# POWER_SUPPLY_20V_4A.net
KiCad netlist of a schematic drawn in Altium Designer
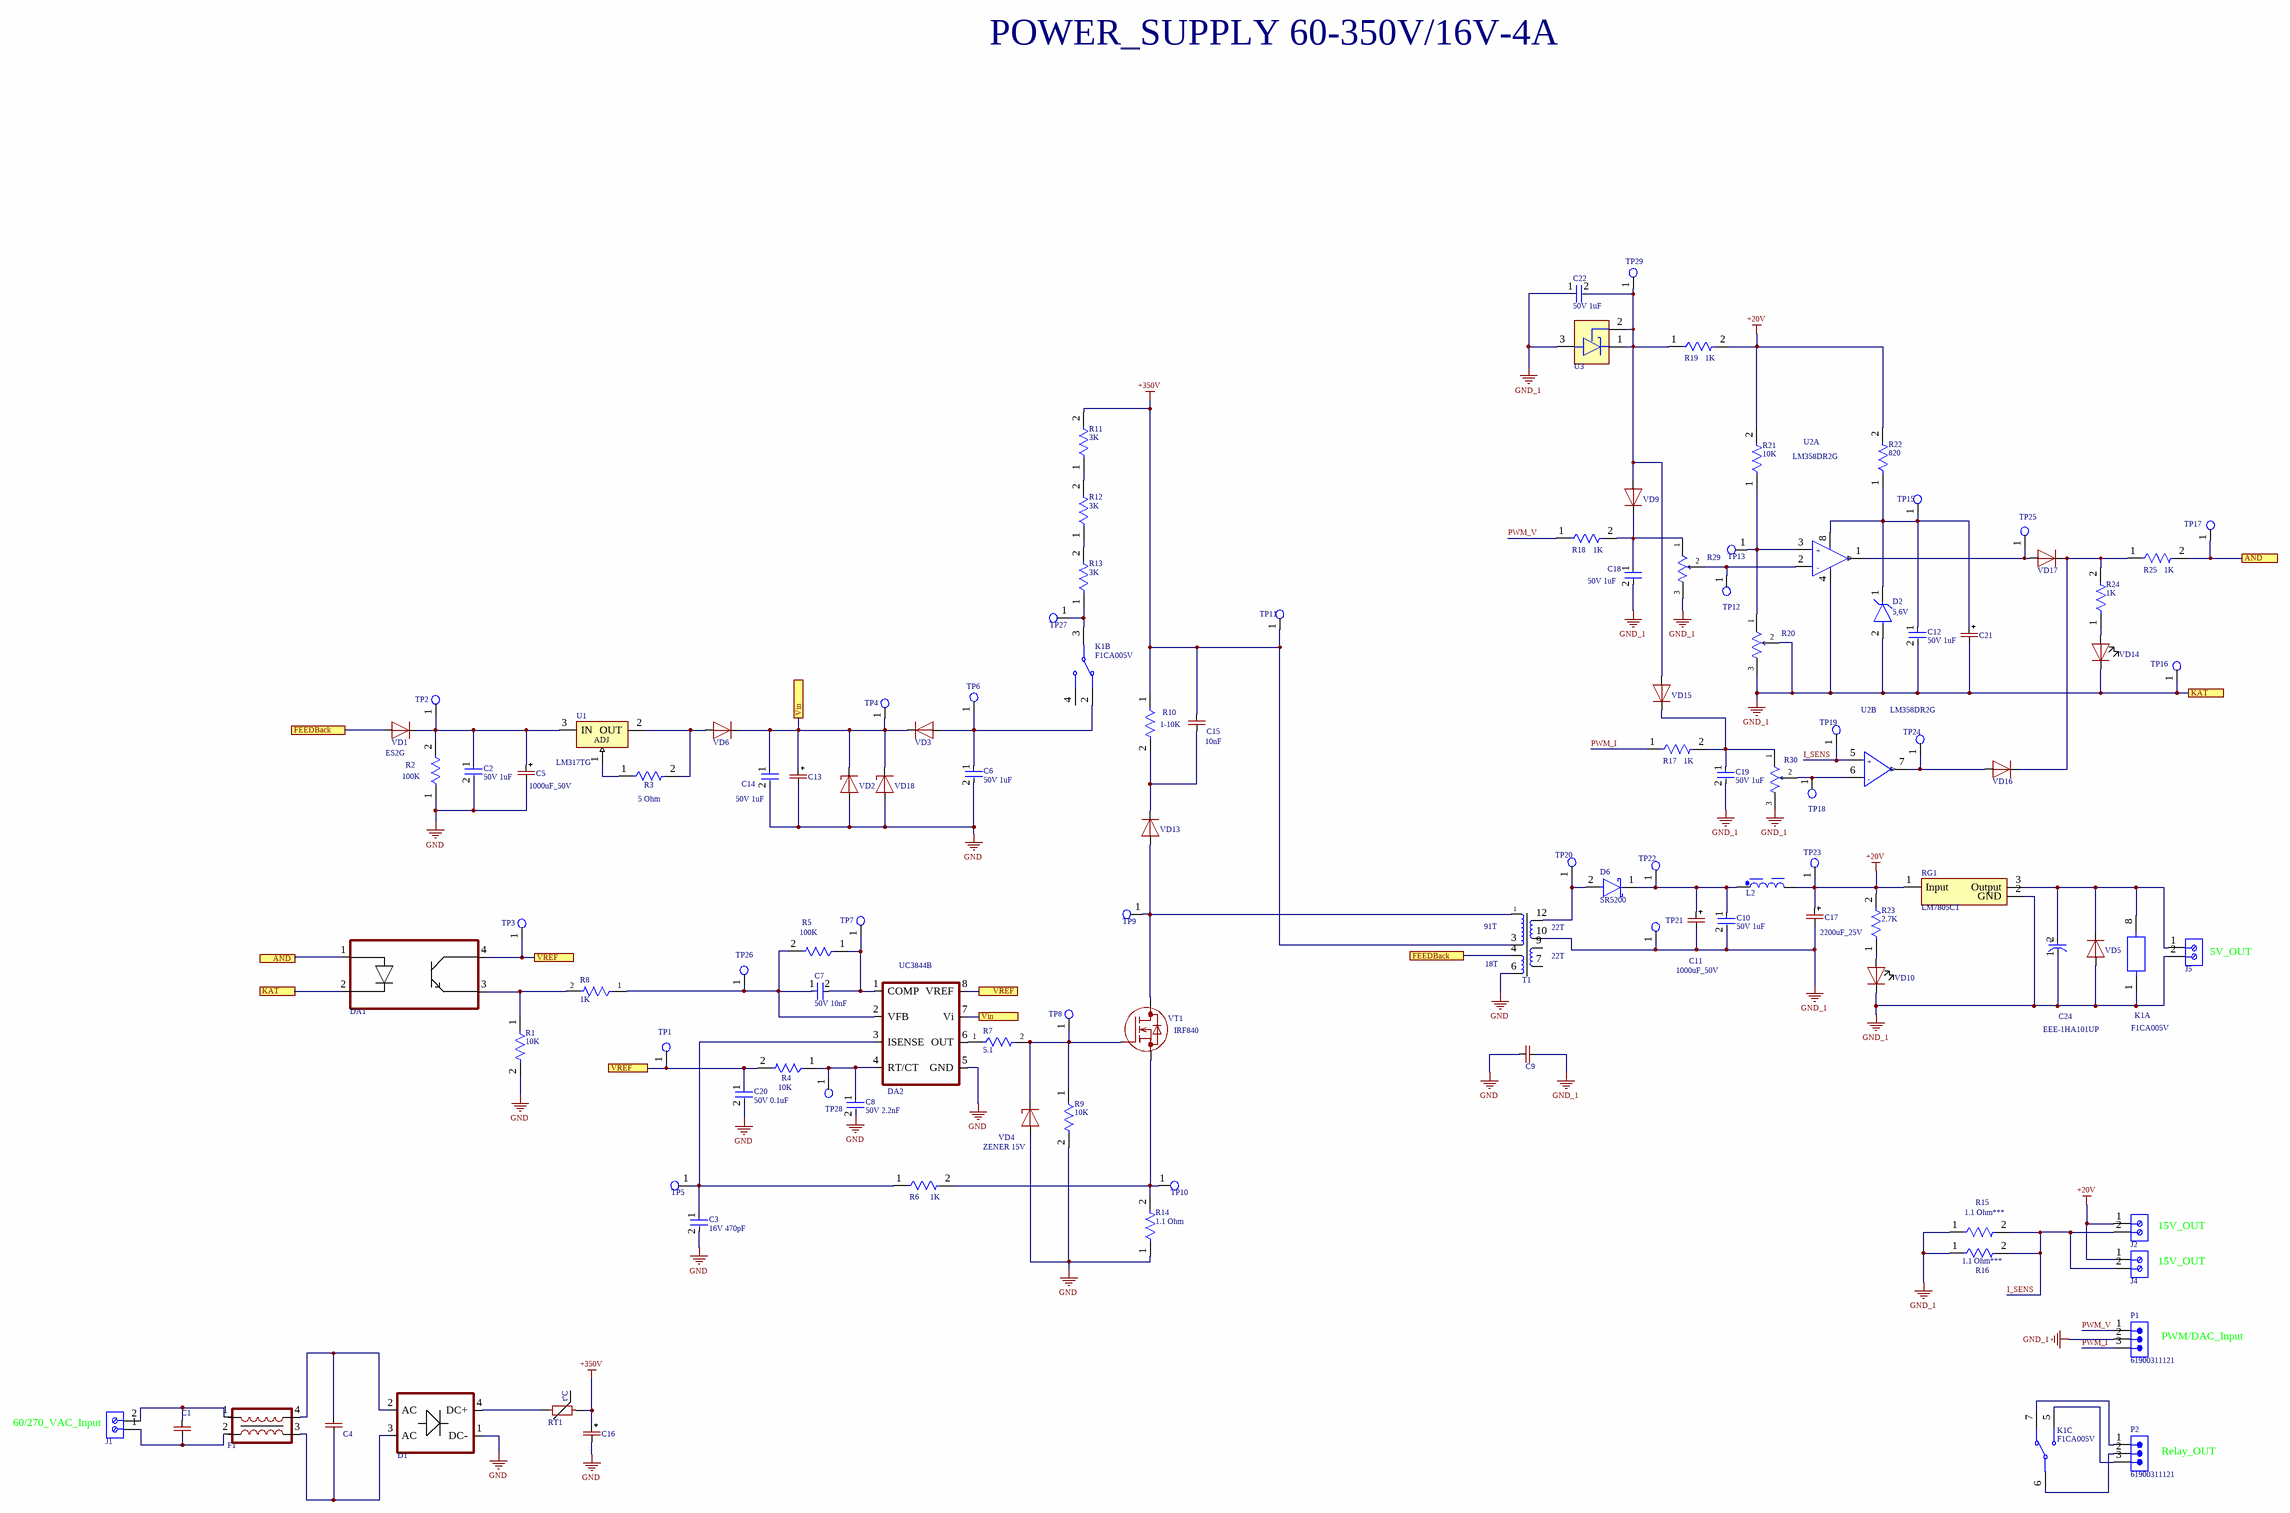
[diagram p0: POWER_SUPPLY_20V_4A.SchDoc]

(export (version "E")
  (design (tool "Eeschema 10.0.6"))
  (components
    (comp (ref "C1")
      (value "CAP-NON-POLAR")
      (footprint "CAP-V15")
      (libsource (lib "0.47uF 310V") (part "CAP-NON-POLAR"))
    )
    (comp (ref "C2")
      (value "50V 1uF")
      (footprint "FP-C0805C-DN-IPC_A")
      (description "CAP CER 0.22UF 50V X7R 0805")
      (fields
        (field (name "MANUFACTURER") "KEMET")
        (field (name "OCTOPART") "https://octopart.com/c0805c224k5ractu-kemet-144670")
      )
      (libsource (lib "Pasive_components") (part "CMP-1036-04552-2"))
    )
    (comp (ref "C3")
      (value "16V 470pF")
      (footprint "FP-C0805C-DN-IPC_A")
      (description "CAP CER 0.22UF 50V X7R 0805")
      (fields
        (field (name "MANUFACTURER") "KEMET")
        (field (name "OCTOPART") "https://octopart.com/c0805c224k5ractu-kemet-144670")
      )
      (libsource (lib "Pasive_components") (part "CMP-1036-04552-2"))
    )
    (comp (ref "C4")
      (value "CAP-NON-POLAR")
      (footprint "CAP-V15")
      (libsource (lib "0.47uF 310V") (part "CAP-NON-POLAR"))
    )
    (comp (ref "C5")
      (value "1000uF_50V")
      (footprint "CAPPOL-12x25")
      (description "1000uF_50V  12x25(13x26mm)")
      (libsource (lib "PASSIVE_COMPONENTS") (part "CAP-POLAR"))
    )
    (comp (ref "C6")
      (value "50V 1uF")
      (footprint "FP-C0805C-DN-IPC_A")
      (description "CAP CER 0.22UF 50V X7R 0805")
      (fields
        (field (name "MANUFACTURER") "KEMET")
        (field (name "OCTOPART") "https://octopart.com/c0805c224k5ractu-kemet-144670")
      )
      (libsource (lib "Pasive_components") (part "CMP-1036-04552-2"))
    )
    (comp (ref "C7")
      (value "50V 10nF")
      (footprint "FP-C0805C-DN-IPC_A")
      (description "CAP CER 0.22UF 50V X7R 0805")
      (fields
        (field (name "MANUFACTURER") "KEMET")
        (field (name "OCTOPART") "https://octopart.com/c0805c224k5ractu-kemet-144670")
      )
      (libsource (lib "Pasive_components") (part "CMP-1036-04552-2"))
    )
    (comp (ref "C8")
      (value "50V 2.2nF")
      (footprint "FP-C0805C-DN-IPC_A")
      (description "CAP CER 2.2nF 50V X7R 0805")
      (fields
        (field (name "MANUFACTURER") "KEMET")
        (field (name "OCTOPART") "https://octopart.com/c0805c224k5ractu-kemet-144670")
      )
      (libsource (lib "Pasive_components") (part "CMP-1036-04552-2"))
    )
    (comp (ref "C9") (value "CAP-V") (footprint "CAP-V") (libsource (lib "2200") (part "CAP-V")))
    (comp (ref "C10")
      (value "50V 1uF")
      (footprint "FP-C0805C-DN-IPC_A")
      (description "CAP CER 0.22UF 50V X7R 0805")
      (fields
        (field (name "MANUFACTURER") "KEMET")
        (field (name "OCTOPART") "https://octopart.com/c0805c224k5ractu-kemet-144670")
      )
      (libsource (lib "Pasive_components") (part "CMP-1036-04552-2"))
    )
    (comp (ref "C11")
      (value "1000uF_50V")
      (footprint "CAPPOL-12x25")
      (libsource (lib "PASSIVE_COMPONENTS") (part "CAP-POLAR"))
    )
    (comp (ref "C12")
      (value "50V 1uF")
      (footprint "FP-C0805C-DN-IPC_A")
      (description "CAP CER 0.22UF 50V X7R 0805")
      (fields
        (field (name "MANUFACTURER") "KEMET")
        (field (name "OCTOPART") "https://octopart.com/c0805c224k5ractu-kemet-144670")
      )
      (libsource (lib "Pasive_components") (part "CMP-1036-04552-2"))
    )
    (comp (ref "C13")
      (value "CAP-POLAR")
      (footprint "CAPPOL-12x25")
      (libsource (lib "PASSIVE_COMPONENTS") (part "CAP-POLAR"))
    )
    (comp (ref "C14")
      (value "50V 1uF")
      (footprint "FP-C0805C-DN-IPC_A")
      (description "CAP CER 0.22UF 50V X7R 0805")
      (fields
        (field (name "MANUFACTURER") "KEMET")
        (field (name "OCTOPART") "https://octopart.com/c0805c224k5ractu-kemet-144670")
      )
      (libsource (lib "Pasive_components") (part "CMP-1036-04552-2"))
    )
    (comp (ref "C15") (value "10nF") (footprint "CAP-V") (libsource (lib "2200") (part "CAP-V")))
    (comp (ref "C16")
      (value "CAP-POLAR")
      (footprint "CAP 100uF_500V 22x40mm")
      (libsource (lib "PASSIVE_COMPONENTS") (part "CAP-POLAR"))
    )
    (comp (ref "C17")
      (value "2200uF_25V")
      (footprint "CAPPOL-12x25")
      (libsource (lib "PASSIVE_COMPONENTS") (part "CAP-POLAR"))
    )
    (comp (ref "C18")
      (value "50V 1uF")
      (footprint "FP-C0805C-DN-IPC_A")
      (description "CAP CER 0.22UF 50V X7R 0805")
      (fields
        (field (name "MANUFACTURER") "KEMET")
        (field (name "OCTOPART") "https://octopart.com/c0805c224k5ractu-kemet-144670")
      )
      (libsource (lib "Pasive_components") (part "CMP-1036-04552-2"))
    )
    (comp (ref "C19")
      (value "50V 1uF")
      (footprint "FP-C0805C-DN-IPC_A")
      (description "CAP CER 0.22UF 50V X7R 0805")
      (fields
        (field (name "MANUFACTURER") "KEMET")
        (field (name "OCTOPART") "https://octopart.com/c0805c224k5ractu-kemet-144670")
      )
      (libsource (lib "Pasive_components") (part "CMP-1036-04552-2"))
    )
    (comp (ref "C20")
      (value "50V 0.1uF")
      (footprint "FP-C0805C-DN-IPC_A")
      (description "CAP CER 0.1UF 50V X7R 0805")
      (fields
        (field (name "MANUFACTURER") "KEMET")
        (field (name "OCTOPART") "https://octopart.com/c0805c224k5ractu-kemet-144670")
      )
      (libsource (lib "Pasive_components") (part "CMP-1036-04552-2"))
    )
    (comp (ref "C21")
      (value "CAP-POLAR")
      (footprint "CAP-TAN-C")
      (libsource (lib "PASSIVE_COMPONENTS") (part "CAP-POLAR"))
    )
    (comp (ref "C22")
      (value "50V 1uF")
      (footprint "FP-C0805C-DN-IPC_A")
      (description "CAP CER 0.22UF 50V X7R 0805")
      (fields
        (field (name "MANUFACTURER") "KEMET")
        (field (name "OCTOPART") "https://octopart.com/c0805c224k5ractu-kemet-144670")
      )
      (libsource (lib "Pasive_components") (part "CMP-1036-04552-2"))
    )
    (comp (ref "C24")
      (value "EEE-1HA101UP")
      (footprint "FP-SF-MFG")
      (description "CAP ALUM 100UF 20% 50V SMD")
      (fields
        (field (name "MANUFACTURER") "Panasonic")
        (field (name "OCTOPART") "https://octopart.com/eee-1ha101up-panasonic-55396734")
      )
      (libsource (lib "Pasive_components") (part "CMP-05427-000015-1"))
    )
    (comp (ref "D1") (value "RS40X") (footprint "RS40X") (libsource (lib "RS40X") (part "RS40X")))
    (comp (ref "D2")
      (value "5,6V")
      (footprint "FP-SB-V-3906_04-031_4-MFG")
      (description "DIODE ZENER 8.2V 500MW DO35")
      (fields (field (name "TOLERANCE") "2%"))
      (libsource (lib "Altium Content Vault") (part "f813f71cba58e380607f5dd3caf9714"))
    )
    (comp (ref "D6")
      (value "SR5200")
      (footprint "SR5100(DO-201AD")
      (libsource (lib "SR5100") (part "SR5100"))
    )
    (comp (ref "DA1") (value "PC817") (footprint "4-SMD") (libsource (lib "PC817") (part "PC817")))
    (comp (ref "DA2") (value "UC3844B") (footprint "SOIC8-150") (libsource (lib "UC3842B") (part "UC3842B")))
    (comp (ref "F1") (value "FILTER") (footprint "FILTER_1") (libsource (lib "FILTER") (part "FILTER")))
    (comp (ref "J1")
      (value "691101710002")
      (footprint "691101710002")
      (description "WR-TBL Series 101 Horizontal Entry Modular, THT, pitch 5mm, 2p")
      (fields (field (name "MANUFACTURER") "Wurth Elektronik"))
      (libsource (lib "Altium_WR-TBL (rev22b)") (part "691101710002"))
    )
    (comp (ref "J2")
      (value "~")
      (footprint "691101710002")
      (description "WR-TBL Series 101 Horizontal Entry Modular, THT, pitch 5mm, 2p")
      (fields
        (field (name "MANUFACTURER PART NUMBER") "691101710002")
        (field (name "MANUFACTURER") "Wurth Elektronik")
      )
      (libsource (lib "Altium_WR-TBL (rev23d)") (part "691101710002"))
    )
    (comp (ref "J4")
      (value "691101710002")
      (footprint "691101710002")
      (description "WR-TBL Series 101 Horizontal Entry Modular, THT, pitch 5mm, 2p")
      (fields (field (name "MANUFACTURER") "Wurth Elektronik"))
      (libsource (lib "Altium_WR-TBL (rev23d)") (part "691101710002"))
    )
    (comp (ref "J5")
      (value "691101710002")
      (footprint "691101710002")
      (description "WR-TBL Series 101 Horizontal Entry Modular, THT, pitch 5mm, 2p")
      (fields (field (name "MANUFACTURER") "Wurth Elektronik"))
      (libsource (lib "Altium_WR-TBL (rev23f)") (part "691101710002"))
    )
    (comp (ref "K1")
      (value "F1CA005V")
      (footprint "Relay_F1CA005V_Omron")
      (libsource (lib "Relay_F1CA005V") (part "F1CA005V"))
    )
    (comp (ref "L2")
      (value "1.2µH, 7.4A")
      (footprint "WE-PD2_1054")
      (description "WE-PD2 SMT Power Inductor, size 1054, 1.2µH, 7.4A, 0.006Ω")
      (fields
        (field (name "MANUFACTURER PART NUMBER") "744776012")
        (field (name "MANUFACTURER") "Wurth Elektronik")
      )
      (libsource (lib "WE-PD2 (rev22d)") (part "744776012"))
    )
    (comp (ref "P1")
      (value "61900311121")
      (footprint "61900311121")
      (description "WR-WTB THT Male Vertical Locking Header, pitch 2.54mm, 3pins")
      (fields (field (name "MANUFACTURER") "Wurth Elektronik"))
      (libsource (lib "Altium_WR-WTB (rev22b)") (part "61900311121"))
    )
    (comp (ref "P2")
      (value "61900311121")
      (footprint "61900311121")
      (description "WR-WTB THT Male Vertical Locking Header, pitch 2.54mm, 3pins")
      (fields (field (name "MANUFACTURER") "Wurth Elektronik"))
      (libsource (lib "Altium_WR-WTB (rev22b)") (part "61900311121"))
    )
    (comp (ref "R1")
      (value "10K")
      (footprint "RES-0805")
      (libsource (lib "PASSIVE_COMPONENTS") (part "RES-CONST"))
    )
    (comp (ref "R2")
      (value "100K")
      (footprint "RES-0805")
      (libsource (lib "PASSIVE_COMPONENTS") (part "RES-CONST"))
    )
    (comp (ref "R3")
      (value "5 Ohm")
      (footprint "RES-0805")
      (libsource (lib "PASSIVE_COMPONENTS") (part "RES-CONST"))
    )
    (comp (ref "R4")
      (value "10K")
      (footprint "RES-0805")
      (libsource (lib "PASSIVE_COMPONENTS") (part "RES-CONST"))
    )
    (comp (ref "R5")
      (value "100K")
      (footprint "RES-0805")
      (libsource (lib "PASSIVE_COMPONENTS") (part "RES-CONST"))
    )
    (comp (ref "R6")
      (value "1K")
      (footprint "RES-0805")
      (libsource (lib "PASSIVE_COMPONENTS") (part "RES-CONST"))
    )
    (comp (ref "R7")
      (value "5.1")
      (footprint "Vishay_CRCW0805-e3_IPC_A")
      (libsource (lib "Res_Vishay_CRCW08050000Z0EA_eec") (part "CRCW08050000Z0EA"))
    )
    (comp (ref "R8")
      (value "1K")
      (footprint "Vishay_CRCW0805-e3_IPC_A")
      (libsource (lib "Res_Vishay_CRCW08050000Z0EA_eec") (part "CRCW08050000Z0EA"))
    )
    (comp (ref "R9")
      (value "10K")
      (footprint "RES-0805")
      (libsource (lib "PASSIVE_COMPONENTS") (part "RES-CONST"))
    )
    (comp (ref "R10")
      (value "1-10K")
      (footprint "RES-2512")
      (description "10K")
      (libsource (lib "PASSIVE_COMPONENTS") (part "RES-CONST"))
    )
    (comp (ref "R11")
      (value "3K")
      (footprint "RES-2512")
      (libsource (lib "PASSIVE_COMPONENTS") (part "RES-CONST"))
    )
    (comp (ref "R12")
      (value "3K")
      (footprint "RES-2512")
      (libsource (lib "PASSIVE_COMPONENTS") (part "RES-CONST"))
    )
    (comp (ref "R13")
      (value "3K")
      (footprint "RES-2512")
      (libsource (lib "PASSIVE_COMPONENTS") (part "RES-CONST"))
    )
    (comp (ref "R14")
      (value "1.1 Ohm")
      (footprint "RES-2W")
      (libsource (lib "PASSIVE_COMPONENTS") (part "RES-CONST"))
    )
    (comp (ref "R15")
      (value "1.1 Ohm***")
      (footprint "RES-2W_2")
      (description "10K")
      (libsource (lib "PASSIVE_COMPONENTS") (part "RES-CONST"))
    )
    (comp (ref "R16")
      (value "1.1 Ohm***")
      (footprint "RES-2W_2")
      (description "10K")
      (libsource (lib "PASSIVE_COMPONENTS") (part "RES-CONST"))
    )
    (comp (ref "R17")
      (value "1K")
      (footprint "RES-0805")
      (libsource (lib "PASSIVE_COMPONENTS") (part "RES-CONST"))
    )
    (comp (ref "R18")
      (value "1K")
      (footprint "RES-0805")
      (libsource (lib "PASSIVE_COMPONENTS") (part "RES-CONST"))
    )
    (comp (ref "R19")
      (value "1K")
      (footprint "RES-0805")
      (libsource (lib "PASSIVE_COMPONENTS") (part "RES-CONST"))
    )
    (comp (ref "R20")
      (value "3296W-1-202LF")
      (footprint "Bourns_3296W_MFG")
      (libsource (lib "Pasive_components") (part "3296W-1-202LF"))
    )
    (comp (ref "R21")
      (value "10K")
      (footprint "RES-0805")
      (libsource (lib "PASSIVE_COMPONENTS") (part "RES-CONST"))
    )
    (comp (ref "R22")
      (value "820")
      (footprint "RES-0805")
      (libsource (lib "PASSIVE_COMPONENTS") (part "RES-CONST"))
    )
    (comp (ref "R23")
      (value "2.7K")
      (footprint "RES-0805")
      (libsource (lib "PASSIVE_COMPONENTS") (part "RES-CONST"))
    )
    (comp (ref "R24")
      (value "1K")
      (footprint "RES-0805")
      (libsource (lib "PASSIVE_COMPONENTS") (part "RES-CONST"))
    )
    (comp (ref "R25")
      (value "1K")
      (footprint "RES-0805")
      (libsource (lib "PASSIVE_COMPONENTS") (part "RES-CONST"))
    )
    (comp (ref "R29")
      (value "3296W-1-202LF")
      (footprint "Bourns_3296W_MFG")
      (libsource (lib "Pasive_components") (part "3296W-1-202LF"))
    )
    (comp (ref "R30")
      (value "3296W-1-202LF")
      (footprint "Bourns_3296W_MFG")
      (libsource (lib "Pasive_components") (part "3296W-1-202LF"))
    )
    (comp (ref "RG1")
      (value "LM7805CT")
      (footprint "TO-220_Bended_Rad")
      (description "REG IC REG LINEAR 5V 1A TO220AB")
      (fields
        (field (name "MANUFACTURER") "Fairchild")
        (field (name "MOUSER PART NUMBER") "512-LM7805CT")
        (field (name "PART NUMBER") "LM7805CT")
      )
      (libsource (lib "LM7805") (part "LM7805CT"))
    )
    (comp (ref "RT1") (value "RES-TEMP") (footprint "RES-V5") (libsource (lib "termistor") (part "RES-TEMP")))
    (comp (ref "T1")
      (value "ETD29")
      (footprint "ETD29_Transformer")
      (libsource (lib "ETD_29") (part "Trans_ETD59"))
    )
    (comp (ref "TP1")
      (value "Test_Point_PCB")
      (footprint "Test_Point")
      (description "Test_Point")
      (libsource (lib "Test_Point") (part "TP_PCB?"))
    )
    (comp (ref "TP2")
      (value "Test_Point_PCB")
      (footprint "Test_Point")
      (description "Test_Point")
      (libsource (lib "Test_Point") (part "TP_PCB?"))
    )
    (comp (ref "TP3")
      (value "Test_Point_PCB")
      (footprint "Test_Point")
      (description "Test_Point")
      (libsource (lib "Test_Point") (part "TP_PCB?"))
    )
    (comp (ref "TP4")
      (value "Test_Point_PCB")
      (footprint "Test_Point")
      (description "Test_Point")
      (libsource (lib "Test_Point") (part "TP_PCB?"))
    )
    (comp (ref "TP5")
      (value "Test_Point_PCB")
      (footprint "Test_Point")
      (description "Test_Point")
      (libsource (lib "Test_Point") (part "TP_PCB?"))
    )
    (comp (ref "TP6")
      (value "Test_Point_PCB")
      (footprint "Test_Point")
      (description "Test_Point")
      (libsource (lib "Test_Point") (part "TP_PCB?"))
    )
    (comp (ref "TP7")
      (value "Test_Point_PCB")
      (footprint "Test_Point")
      (description "Test_Point")
      (libsource (lib "Test_Point") (part "TP_PCB?"))
    )
    (comp (ref "TP8")
      (value "Test_Point_PCB")
      (footprint "Test_Point")
      (description "Test_Point")
      (libsource (lib "Test_Point") (part "TP_PCB?"))
    )
    (comp (ref "TP9")
      (value "Test_Point_PCB")
      (footprint "Test_Point")
      (description "Test_Point")
      (libsource (lib "Test_Point") (part "TP_PCB?"))
    )
    (comp (ref "TP10")
      (value "Test_Point_PCB")
      (footprint "Test_Point")
      (description "Test_Point")
      (libsource (lib "Test_Point") (part "TP_PCB?"))
    )
    (comp (ref "TP11")
      (value "Test_Point_PCB")
      (footprint "Test_Point")
      (description "Test_Point")
      (libsource (lib "Test_Point") (part "TP_PCB?"))
    )
    (comp (ref "TP12")
      (value "Test_Point_PCB")
      (footprint "Test_Point")
      (description "Test_Point")
      (libsource (lib "Test_Point") (part "TP_PCB?"))
    )
    (comp (ref "TP13")
      (value "Test_Point_PCB")
      (footprint "Test_Point")
      (description "Test_Point")
      (libsource (lib "Test_Point") (part "TP_PCB?"))
    )
    (comp (ref "TP15")
      (value "Test_Point_PCB")
      (footprint "Test_Point")
      (description "Test_Point")
      (libsource (lib "Test_Point") (part "TP_PCB?"))
    )
    (comp (ref "TP16")
      (value "Test_Point_PCB")
      (footprint "Test_Point")
      (description "Test_Point")
      (libsource (lib "Test_Point") (part "TP_PCB?"))
    )
    (comp (ref "TP17")
      (value "Test_Point_PCB")
      (footprint "Test_Point")
      (description "Test_Point")
      (libsource (lib "Test_Point") (part "TP_PCB?"))
    )
    (comp (ref "TP18")
      (value "Test_Point_PCB")
      (footprint "Test_Point")
      (description "Test_Point")
      (libsource (lib "Test_Point") (part "TP_PCB?"))
    )
    (comp (ref "TP19")
      (value "Test_Point_PCB")
      (footprint "Test_Point")
      (description "Test_Point")
      (libsource (lib "Test_Point") (part "TP_PCB?"))
    )
    (comp (ref "TP20")
      (value "Test_Point_PCB")
      (footprint "Test_Point")
      (description "Test_Point")
      (libsource (lib "Test_Point") (part "TP_PCB?"))
    )
    (comp (ref "TP21")
      (value "Test_Point_PCB")
      (footprint "Test_Point")
      (description "Test_Point")
      (libsource (lib "Test_Point") (part "TP_PCB?"))
    )
    (comp (ref "TP22")
      (value "Test_Point_PCB")
      (footprint "Test_Point")
      (description "Test_Point")
      (libsource (lib "Test_Point") (part "TP_PCB?"))
    )
    (comp (ref "TP23")
      (value "Test_Point_PCB")
      (footprint "Test_Point")
      (description "Test_Point")
      (libsource (lib "Test_Point") (part "TP_PCB?"))
    )
    (comp (ref "TP24")
      (value "Test_Point_PCB")
      (footprint "Test_Point")
      (description "Test_Point")
      (libsource (lib "Test_Point") (part "TP_PCB?"))
    )
    (comp (ref "TP25")
      (value "Test_Point_PCB")
      (footprint "Test_Point")
      (description "Test_Point")
      (libsource (lib "Test_Point") (part "TP_PCB?"))
    )
    (comp (ref "TP26")
      (value "Test_Point_PCB")
      (footprint "Test_Point")
      (description "Test_Point")
      (libsource (lib "Test_Point") (part "TP_PCB?"))
    )
    (comp (ref "TP27")
      (value "Test_Point_PCB")
      (footprint "Test_Point")
      (description "Test_Point")
      (libsource (lib "Test_Point") (part "TP_PCB?"))
    )
    (comp (ref "TP28")
      (value "Test_Point_PCB")
      (footprint "Test_Point")
      (description "Test_Point")
      (libsource (lib "Test_Point") (part "TP_PCB?"))
    )
    (comp (ref "TP29")
      (value "Test_Point_PCB")
      (footprint "Test_Point")
      (description "Test_Point")
      (libsource (lib "Test_Point") (part "TP_PCB?"))
    )
    (comp (ref "U1")
      (value "LM317TG")
      (footprint "TO-220_Bended_Rad")
      (libsource (lib "LM317TG") (part "LM317TG"))
    )
    (comp (ref "U2")
      (value "LM358DR2G")
      (footprint "FP-751-07-IPC_C")
      (description "IC OPAMP GP 2 CIRCUIT 8SOIC")
      (libsource (lib "Altium Content Vault") (part "992a6607d1d88c80ee6b45e5ba6cb1b"))
    )
    (comp (ref "U3")
      (value "TL431")
      (footprint "TL431_SOT-23-3(MGF)")
      (description "TL431_SOT-23-3")
      (libsource (lib "TL431") (part "TL431_SOT-23-3"))
    )
    (comp (ref "VD1") (value "ES2G") (footprint "DO-214AC, SMA") (libsource (lib "DO214") (part "DIODE")))
    (comp (ref "VD2") (value "ZENER") (footprint "DO-017AA") (libsource (lib "ZENER") (part "ZENER")))
    (comp (ref "VD3") (value "DIODE") (footprint "DO-214AC, SMA") (libsource (lib "DO214") (part "DIODE")))
    (comp (ref "VD4") (value "ZENER 15V") (footprint "DO-017AA") (libsource (lib "ZENER") (part "ZENER")))
    (comp (ref "VD5") (value "DIODE") (footprint "SOD-123") (libsource (lib "4148") (part "DIODE")))
    (comp (ref "VD6") (value "DIODE") (footprint "DO-214AC, SMA") (libsource (lib "DO214") (part "DIODE")))
    (comp (ref "VD9") (value "DIODE") (footprint "SOD-123") (libsource (lib "4148") (part "DIODE")))
    (comp (ref "VD10") (value "LED") (footprint "LED-0603") (libsource (lib "LED") (part "LED")))
    (comp (ref "VD13") (value "DIODE") (footprint "DO-214AC, SMA") (libsource (lib "DO214") (part "DIODE")))
    (comp (ref "VD14") (value "LED") (footprint "LED-0603") (libsource (lib "LED") (part "LED")))
    (comp (ref "VD15") (value "DIODE") (footprint "SOD-123") (libsource (lib "4148") (part "DIODE")))
    (comp (ref "VD16") (value "DIODE") (footprint "SOD-123") (libsource (lib "4148") (part "DIODE")))
    (comp (ref "VD17") (value "DIODE") (footprint "SOD-123") (libsource (lib "4148") (part "DIODE")))
    (comp (ref "VD18") (value "ZENER") (footprint "DO-017AA") (libsource (lib "ZENER") (part "ZENER")))
    (comp (ref "VT1")
      (value "IRF840")
      (footprint "TO-220_Bended_Rad")
      (libsource (lib "IRF640") (part "MOSFET-N-GDS"))
    )
  )
  (nets
    (net (code "1") (name "+20V") (class "Default")
      (node (ref "C17") (pin "1") (pinfunction "+_1") (pintype "passive"))
      (node (ref "J2") (pin "1") (pinfunction "1_1") (pintype "passive"))
      (node (ref "J4") (pin "1") (pinfunction "1_1") (pintype "passive"))
      (node (ref "L2") (pin "2") (pinfunction "2_2") (pintype "passive"))
      (node (ref "R19") (pin "2") (pinfunction "2_2") (pintype "passive"))
      (node (ref "R21") (pin "2") (pinfunction "2_2") (pintype "passive"))
      (node (ref "R22") (pin "2") (pinfunction "2_2") (pintype "passive"))
      (node (ref "R23") (pin "2") (pinfunction "2_2") (pintype "passive"))
      (node (ref "RG1") (pin "1") (pinfunction "Input_1") (pintype "power_in"))
      (node (ref "TP23") (pin "1") (pinfunction "G9_1") (pintype "passive"))
    )
    (net (code "2") (name "+350V") (class "Default")
      (node (ref "C15") (pin "2") (pinfunction "2_2") (pintype "passive"))
      (node (ref "C16") (pin "1") (pinfunction "+_1") (pintype "passive"))
      (node (ref "R10") (pin "1") (pinfunction "1_1") (pintype "passive"))
      (node (ref "R11") (pin "2") (pinfunction "2_2") (pintype "passive"))
      (node (ref "RT1") (pin "1") (pinfunction "1_1") (pintype "passive"))
      (node (ref "T1") (pin "3") (pinfunction "3_3") (pintype "passive"))
      (node (ref "TP11") (pin "1") (pinfunction "G9_1") (pintype "passive"))
    )
    (net (code "3") (name "/AND") (class "Default")
      (node (ref "DA1") (pin "1") (pinfunction "ANODE_1") (pintype "passive"))
      (node (ref "R25") (pin "2") (pinfunction "2_2") (pintype "passive"))
      (node (ref "TP17") (pin "1") (pinfunction "G9_1") (pintype "passive"))
    )
    (net (code "4") (name "/FEEDBack") (class "Default")
      (node (ref "T1") (pin "4") (pinfunction "4_4") (pintype "passive"))
      (node (ref "VD1") (pin "2") (pinfunction "A_2") (pintype "passive"))
    )
    (net (code "5") (name "/I_SENS") (class "Default")
      (node (ref "J2") (pin "2") (pinfunction "2_2") (pintype "passive"))
      (node (ref "J4") (pin "2") (pinfunction "2_2") (pintype "passive"))
      (node (ref "R15") (pin "2") (pinfunction "2_2") (pintype "passive"))
      (node (ref "R16") (pin "2") (pinfunction "2_2") (pintype "passive"))
      (node (ref "TP19") (pin "1") (pinfunction "G9_1") (pintype "passive"))
      (node (ref "U2") (pin "5") (pinfunction "INPUT_B+_5") (pintype "tri_state"))
    )
    (net (code "6") (name "/PWM_I") (class "Default")
      (node (ref "P1") (pin "3") (pinfunction "3_3") (pintype "passive"))
      (node (ref "R17") (pin "1") (pinfunction "1_1") (pintype "passive"))
    )
    (net (code "7") (name "/PWM_V") (class "Default")
      (node (ref "P1") (pin "1") (pinfunction "1_1") (pintype "passive"))
      (node (ref "R18") (pin "1") (pinfunction "1_1") (pintype "passive"))
    )
    (net (code "8") (name "/VREF") (class "Default")
      (node (ref "C20") (pin "1") (pinfunction "1_1") (pintype "passive"))
      (node (ref "DA1") (pin "4") (pinfunction "COLLECTOR_4") (pintype "passive"))
      (node (ref "DA2") (pin "8") (pinfunction "VREF_8") (pintype "passive"))
      (node (ref "R4") (pin "2") (pinfunction "2_2") (pintype "passive"))
      (node (ref "TP1") (pin "1") (pinfunction "G9_1") (pintype "passive"))
      (node (ref "TP3") (pin "1") (pinfunction "G9_1") (pintype "passive"))
    )
    (net (code "9") (name "/Vin") (class "Default")
      (node (ref "C13") (pin "1") (pinfunction "+_1") (pintype "passive"))
      (node (ref "C14") (pin "1") (pinfunction "1_1") (pintype "passive"))
      (node (ref "DA2") (pin "7") (pinfunction "Vi_7") (pintype "passive"))
      (node (ref "TP4") (pin "1") (pinfunction "G9_1") (pintype "passive"))
      (node (ref "VD18") (pin "1") (pinfunction "C_1") (pintype "passive"))
      (node (ref "VD2") (pin "1") (pinfunction "C_1") (pintype "passive"))
      (node (ref "VD3") (pin "1") (pinfunction "C_1") (pintype "passive"))
      (node (ref "VD6") (pin "1") (pinfunction "C_1") (pintype "passive"))
    )
    (net (code "10") (name "GND") (class "Default")
      (node (ref "C13") (pin "2") (pinfunction "-_2") (pintype "passive"))
      (node (ref "C14") (pin "2") (pinfunction "2_2") (pintype "passive"))
      (node (ref "C16") (pin "2") (pinfunction "-_2") (pintype "passive"))
      (node (ref "C2") (pin "2") (pinfunction "2_2") (pintype "passive"))
      (node (ref "C20") (pin "2") (pinfunction "2_2") (pintype "passive"))
      (node (ref "C3") (pin "2") (pinfunction "2_2") (pintype "passive"))
      (node (ref "C5") (pin "2") (pinfunction "-_2") (pintype "passive"))
      (node (ref "C6") (pin "2") (pinfunction "2_2") (pintype "passive"))
      (node (ref "C8") (pin "2") (pinfunction "2_2") (pintype "passive"))
      (node (ref "C9") (pin "1") (pinfunction "1_1") (pintype "passive"))
      (node (ref "D1") (pin "1") (pinfunction "DC-_1") (pintype "passive"))
      (node (ref "DA2") (pin "5") (pinfunction "GND_5") (pintype "passive"))
      (node (ref "R1") (pin "2") (pinfunction "2_2") (pintype "passive"))
      (node (ref "R14") (pin "1") (pinfunction "1_1") (pintype "passive"))
      (node (ref "R2") (pin "1") (pinfunction "1_1") (pintype "passive"))
      (node (ref "R9") (pin "2") (pinfunction "2_2") (pintype "passive"))
      (node (ref "T1") (pin "6") (pinfunction "6_6") (pintype "passive"))
      (node (ref "VD18") (pin "2") (pinfunction "A_2") (pintype "passive"))
      (node (ref "VD2") (pin "2") (pinfunction "A_2") (pintype "passive"))
      (node (ref "VD4") (pin "2") (pinfunction "A_2") (pintype "passive"))
    )
    (net (code "11") (name "GND_1") (class "Default")
      (node (ref "C10") (pin "2") (pinfunction "2_2") (pintype "passive"))
      (node (ref "C11") (pin "2") (pinfunction "-_2") (pintype "passive"))
      (node (ref "C12") (pin "2") (pinfunction "2_2") (pintype "passive"))
      (node (ref "C17") (pin "2") (pinfunction "-_2") (pintype "passive"))
      (node (ref "C18") (pin "2") (pinfunction "2_2") (pintype "passive"))
      (node (ref "C19") (pin "2") (pinfunction "2_2") (pintype "passive"))
      (node (ref "C21") (pin "2") (pinfunction "-_2") (pintype "passive"))
      (node (ref "C22") (pin "1") (pinfunction "1_1") (pintype "passive"))
      (node (ref "C24") (pin "1") (pinfunction "C_1") (pintype "passive"))
      (node (ref "C9") (pin "2") (pinfunction "2_2") (pintype "passive"))
      (node (ref "D2") (pin "2") (pinfunction "A_2") (pintype "passive"))
      (node (ref "DA1") (pin "2") (pinfunction "CATHODE_2") (pintype "passive"))
      (node (ref "J5") (pin "2") (pinfunction "2_2") (pintype "passive"))
      (node (ref "K1") (pin "1") (pinfunction "1_1") (pintype "passive"))
      (node (ref "P1") (pin "2") (pinfunction "2_2") (pintype "passive"))
      (node (ref "R15") (pin "1") (pinfunction "1_1") (pintype "passive"))
      (node (ref "R16") (pin "1") (pinfunction "1_1") (pintype "passive"))
      (node (ref "R20") (pin "2") (pinfunction "WIPER_2") (pintype "passive"))
      (node (ref "R20") (pin "3") (pinfunction "CW_3") (pintype "passive"))
      (node (ref "R29") (pin "3") (pinfunction "CW_3") (pintype "passive"))
      (node (ref "R30") (pin "3") (pinfunction "CW_3") (pintype "passive"))
      (node (ref "RG1") (pin "2") (pinfunction "GND_2") (pintype "power_in"))
      (node (ref "T1") (pin "10") (pinfunction "10_10") (pintype "passive"))
      (node (ref "TP16") (pin "1") (pinfunction "G9_1") (pintype "passive"))
      (node (ref "TP21") (pin "1") (pinfunction "G9_1") (pintype "passive"))
      (node (ref "U2") (pin "4") (pinfunction "VEE/GND_4") (pintype "power_in"))
      (node (ref "U3") (pin "3") (pinfunction "A_3") (pintype "passive"))
      (node (ref "VD10") (pin "1") (pinfunction "C_1") (pintype "passive"))
      (node (ref "VD14") (pin "1") (pinfunction "C_1") (pintype "passive"))
      (node (ref "VD5") (pin "2") (pinfunction "A_2") (pintype "passive"))
    )
    (net (code "12") (name "Net-(C1-Pad1)") (class "Default")
      (node (ref "C1") (pin "1") (pinfunction "1_1") (pintype "passive"))
      (node (ref "F1") (pin "2") (pinfunction "2_2") (pintype "passive"))
      (node (ref "J1") (pin "1") (pinfunction "1_1") (pintype "passive"))
    )
    (net (code "13") (name "Net-(C1-Pad2)") (class "Default")
      (node (ref "C1") (pin "2") (pinfunction "2_2") (pintype "passive"))
      (node (ref "F1") (pin "1") (pinfunction "1_1") (pintype "passive"))
      (node (ref "J1") (pin "2") (pinfunction "2_2") (pintype "passive"))
    )
    (net (code "14") (name "Net-(C4-Pad1)") (class "Default")
      (node (ref "C4") (pin "1") (pinfunction "1_1") (pintype "passive"))
      (node (ref "D1") (pin "3") (pinfunction "AC_3") (pintype "passive"))
      (node (ref "F1") (pin "3") (pinfunction "3_3") (pintype "passive"))
    )
    (net (code "15") (name "Net-(C4-Pad2)") (class "Default")
      (node (ref "C4") (pin "2") (pinfunction "2_2") (pintype "passive"))
      (node (ref "D1") (pin "2") (pinfunction "AC_2") (pintype "passive"))
      (node (ref "F1") (pin "4") (pinfunction "4_4") (pintype "passive"))
    )
    (net (code "16") (name "Net-(C5-+)") (class "Default")
      (node (ref "C2") (pin "1") (pinfunction "1_1") (pintype "passive"))
      (node (ref "C5") (pin "1") (pinfunction "+_1") (pintype "passive"))
      (node (ref "R2") (pin "2") (pinfunction "2_2") (pintype "passive"))
      (node (ref "TP2") (pin "1") (pinfunction "G9_1") (pintype "passive"))
      (node (ref "U1") (pin "3") (pinfunction "IN_3") (pintype "power_in"))
      (node (ref "VD1") (pin "1") (pinfunction "C_1") (pintype "passive"))
    )
    (net (code "17") (name "Net-(C11-+)") (class "Default")
      (node (ref "C10") (pin "1") (pinfunction "1_1") (pintype "passive"))
      (node (ref "C11") (pin "1") (pinfunction "+_1") (pintype "passive"))
      (node (ref "D6") (pin "1") (pinfunction "C_1") (pintype "passive"))
      (node (ref "L2") (pin "1") (pinfunction "1_1") (pintype "passive"))
      (node (ref "TP22") (pin "1") (pinfunction "G9_1") (pintype "passive"))
    )
    (net (code "18") (name "Net-(C21-+)") (class "Default")
      (node (ref "C12") (pin "1") (pinfunction "1_1") (pintype "passive"))
      (node (ref "C21") (pin "1") (pinfunction "+_1") (pintype "passive"))
      (node (ref "D2") (pin "1") (pinfunction "C_1") (pintype "passive"))
      (node (ref "R22") (pin "1") (pinfunction "1_1") (pintype "passive"))
      (node (ref "TP15") (pin "1") (pinfunction "G9_1") (pintype "passive"))
      (node (ref "U2") (pin "8") (pinfunction "VCC_8") (pintype "power_in"))
    )
    (net (code "19") (name "Net-(C24-A)") (class "Default")
      (node (ref "C24") (pin "2") (pinfunction "A_2") (pintype "passive"))
      (node (ref "J5") (pin "1") (pinfunction "1_1") (pintype "passive"))
      (node (ref "K1") (pin "8") (pinfunction "8_8") (pintype "passive"))
      (node (ref "RG1") (pin "3") (pinfunction "Output_3") (pintype "passive"))
      (node (ref "VD5") (pin "1") (pinfunction "C_1") (pintype "passive"))
    )
    (net (code "20") (name "Net-(D1-DC+)") (class "Default")
      (node (ref "D1") (pin "4") (pinfunction "DC+_4") (pintype "passive"))
      (node (ref "RT1") (pin "2") (pinfunction "2_2") (pintype "passive"))
    )
    (net (code "21") (name "Net-(D6-A)") (class "Default")
      (node (ref "D6") (pin "2") (pinfunction "A_2") (pintype "passive"))
      (node (ref "T1") (pin "12") (pinfunction "12_12") (pintype "passive"))
      (node (ref "TP20") (pin "1") (pinfunction "G9_1") (pintype "passive"))
    )
    (net (code "22") (name "Net-(DA1-EMITTER)") (class "Default")
      (node (ref "DA1") (pin "3") (pinfunction "EMITTER_3") (pintype "passive"))
      (node (ref "R1") (pin "1") (pinfunction "1_1") (pintype "passive"))
      (node (ref "R8") (pin "2") (pinfunction "2_2") (pintype "passive"))
    )
    (net (code "23") (name "Net-(DA2-COMP)") (class "Default")
      (node (ref "C7") (pin "2") (pinfunction "2_2") (pintype "passive"))
      (node (ref "DA2") (pin "1") (pinfunction "COMP_1") (pintype "passive"))
      (node (ref "R5") (pin "1") (pinfunction "1_1") (pintype "passive"))
      (node (ref "TP7") (pin "1") (pinfunction "G9_1") (pintype "passive"))
    )
    (net (code "24") (name "Net-(DA2-ISENSE)") (class "Default")
      (node (ref "C3") (pin "1") (pinfunction "1_1") (pintype "passive"))
      (node (ref "DA2") (pin "3") (pinfunction "ISENSE_3") (pintype "passive"))
      (node (ref "R6") (pin "1") (pinfunction "1_1") (pintype "passive"))
      (node (ref "TP5") (pin "1") (pinfunction "G9_1") (pintype "passive"))
    )
    (net (code "25") (name "Net-(DA2-OUT)") (class "Default")
      (node (ref "DA2") (pin "6") (pinfunction "OUT_6") (pintype "passive"))
      (node (ref "R7") (pin "1") (pinfunction "1_1") (pintype "passive"))
    )
    (net (code "26") (name "Net-(DA2-RT{slash}CT)") (class "Default")
      (node (ref "C8") (pin "1") (pinfunction "1_1") (pintype "passive"))
      (node (ref "DA2") (pin "4") (pinfunction "RT/CT_4") (pintype "passive"))
      (node (ref "R4") (pin "1") (pinfunction "1_1") (pintype "passive"))
      (node (ref "TP28") (pin "1") (pinfunction "G9_1") (pintype "passive"))
    )
    (net (code "27") (name "Net-(DA2-VFB)") (class "Default")
      (node (ref "C7") (pin "1") (pinfunction "1_1") (pintype "passive"))
      (node (ref "DA2") (pin "2") (pinfunction "VFB_2") (pintype "passive"))
      (node (ref "R5") (pin "2") (pinfunction "2_2") (pintype "passive"))
      (node (ref "R8") (pin "1") (pinfunction "1_1") (pintype "passive"))
      (node (ref "TP26") (pin "1") (pinfunction "G9_1") (pintype "passive"))
    )
    (net (code "28") (name "Net-(K1-Pad5)") (class "Default")
      (node (ref "K1") (pin "5") (pinfunction "5_5") (pintype "passive"))
      (node (ref "P2") (pin "3") (pinfunction "3_3") (pintype "passive"))
    )
    (net (code "29") (name "Net-(K1-Pad6)") (class "Default")
      (node (ref "K1") (pin "6") (pinfunction "6_6") (pintype "passive"))
      (node (ref "P2") (pin "2") (pinfunction "2_2") (pintype "passive"))
    )
    (net (code "30") (name "Net-(K1-Pad7)") (class "Default")
      (node (ref "K1") (pin "7") (pinfunction "7_7") (pintype "passive"))
      (node (ref "P2") (pin "1") (pinfunction "1_1") (pintype "passive"))
    )
    (net (code "31") (name "Net-(R11-Pad1)") (class "Default")
      (node (ref "R11") (pin "1") (pinfunction "1_1") (pintype "passive"))
      (node (ref "R12") (pin "2") (pinfunction "2_2") (pintype "passive"))
    )
    (net (code "32") (name "Net-(R12-Pad1)") (class "Default")
      (node (ref "R12") (pin "1") (pinfunction "1_1") (pintype "passive"))
      (node (ref "R13") (pin "2") (pinfunction "2_2") (pintype "passive"))
    )
    (net (code "33") (name "Net-(R20-CCW)") (class "Default")
      (node (ref "R20") (pin "1") (pinfunction "CCW_1") (pintype "passive"))
      (node (ref "R21") (pin "1") (pinfunction "1_1") (pintype "passive"))
      (node (ref "TP13") (pin "1") (pinfunction "G9_1") (pintype "passive"))
      (node (ref "U2") (pin "3") (pinfunction "INPUT_A+_3") (pintype "tri_state"))
    )
    (net (code "34") (name "Net-(R29-CCW)") (class "Default")
      (node (ref "C18") (pin "1") (pinfunction "1_1") (pintype "passive"))
      (node (ref "R18") (pin "2") (pinfunction "2_2") (pintype "passive"))
      (node (ref "R29") (pin "1") (pinfunction "CCW_1") (pintype "passive"))
      (node (ref "VD9") (pin "1") (pinfunction "C_1") (pintype "passive"))
    )
    (net (code "35") (name "Net-(R29-WIPER)") (class "Default")
      (node (ref "R29") (pin "2") (pinfunction "WIPER_2") (pintype "passive"))
      (node (ref "TP12") (pin "1") (pinfunction "G9_1") (pintype "passive"))
      (node (ref "U2") (pin "2") (pinfunction "INPUT_A-_2") (pintype "tri_state"))
    )
    (net (code "36") (name "Net-(R30-CCW)") (class "Default")
      (node (ref "C19") (pin "1") (pinfunction "1_1") (pintype "passive"))
      (node (ref "R17") (pin "2") (pinfunction "2_2") (pintype "passive"))
      (node (ref "R30") (pin "1") (pinfunction "CCW_1") (pintype "passive"))
      (node (ref "VD15") (pin "1") (pinfunction "C_1") (pintype "passive"))
    )
    (net (code "37") (name "Net-(R30-WIPER)") (class "Default")
      (node (ref "R30") (pin "2") (pinfunction "WIPER_2") (pintype "passive"))
      (node (ref "TP18") (pin "1") (pinfunction "G9_1") (pintype "passive"))
      (node (ref "U2") (pin "6") (pinfunction "INPUT_B-_6") (pintype "tri_state"))
    )
    (net (code "38") (name "Net-(TP6-G9)") (class "Default")
      (node (ref "C6") (pin "1") (pinfunction "1_1") (pintype "passive"))
      (node (ref "K1") (pin "2") (pinfunction "2_2") (pintype "passive"))
      (node (ref "TP6") (pin "1") (pinfunction "G9_1") (pintype "passive"))
      (node (ref "VD3") (pin "2") (pinfunction "A_2") (pintype "passive"))
    )
    (net (code "39") (name "Net-(TP8-G9)") (class "Default")
      (node (ref "R7") (pin "2") (pinfunction "2_2") (pintype "passive"))
      (node (ref "R9") (pin "1") (pinfunction "1_1") (pintype "passive"))
      (node (ref "TP8") (pin "1") (pinfunction "G9_1") (pintype "passive"))
      (node (ref "VD4") (pin "1") (pinfunction "C_1") (pintype "passive"))
      (node (ref "VT1") (pin "1") (pinfunction "G_1") (pintype "passive"))
    )
    (net (code "40") (name "Net-(TP9-G9)") (class "Default")
      (node (ref "T1") (pin "1") (pinfunction "1_1") (pintype "passive"))
      (node (ref "TP9") (pin "1") (pinfunction "G9_1") (pintype "passive"))
      (node (ref "VD13") (pin "2") (pinfunction "A_2") (pintype "passive"))
      (node (ref "VT1") (pin "2") (pinfunction "D_2") (pintype "passive"))
    )
    (net (code "41") (name "Net-(TP10-G9)") (class "Default")
      (node (ref "R14") (pin "2") (pinfunction "2_2") (pintype "passive"))
      (node (ref "R6") (pin "2") (pinfunction "2_2") (pintype "passive"))
      (node (ref "TP10") (pin "1") (pinfunction "G9_1") (pintype "passive"))
      (node (ref "VT1") (pin "3") (pinfunction "S_3") (pintype "passive"))
    )
    (net (code "42") (name "Net-(TP24-G9)") (class "Default")
      (node (ref "TP24") (pin "1") (pinfunction "G9_1") (pintype "passive"))
      (node (ref "U2") (pin "7") (pinfunction "OUTPUT_B_7") (pintype "output"))
      (node (ref "VD16") (pin "2") (pinfunction "A_2") (pintype "passive"))
    )
    (net (code "43") (name "Net-(TP25-G9)") (class "Default")
      (node (ref "TP25") (pin "1") (pinfunction "G9_1") (pintype "passive"))
      (node (ref "U2") (pin "1") (pinfunction "OUTPUT_A_1") (pintype "output"))
      (node (ref "VD17") (pin "2") (pinfunction "A_2") (pintype "passive"))
    )
    (net (code "44") (name "Net-(TP27-G9)") (class "Default")
      (node (ref "K1") (pin "3") (pinfunction "3_3") (pintype "passive"))
      (node (ref "R13") (pin "1") (pinfunction "1_1") (pintype "passive"))
      (node (ref "TP27") (pin "1") (pinfunction "G9_1") (pintype "passive"))
    )
    (net (code "45") (name "Net-(TP29-G9)") (class "Default")
      (node (ref "C22") (pin "2") (pinfunction "2_2") (pintype "passive"))
      (node (ref "R19") (pin "1") (pinfunction "1_1") (pintype "passive"))
      (node (ref "TP29") (pin "1") (pinfunction "G9_1") (pintype "passive"))
      (node (ref "U3") (pin "1") (pinfunction "C_1") (pintype "passive"))
      (node (ref "U3") (pin "2") (pinfunction "REF_2") (pintype "passive"))
      (node (ref "VD15") (pin "2") (pinfunction "A_2") (pintype "passive"))
      (node (ref "VD9") (pin "2") (pinfunction "A_2") (pintype "passive"))
    )
    (net (code "46") (name "Net-(U1-ADJ)") (class "Default")
      (node (ref "R3") (pin "1") (pinfunction "1_1") (pintype "passive"))
      (node (ref "U1") (pin "1") (pinfunction "ADJ_1") (pintype "input"))
    )
    (net (code "47") (name "Net-(U1-OUT)") (class "Default")
      (node (ref "R3") (pin "2") (pinfunction "2_2") (pintype "passive"))
      (node (ref "U1") (pin "2") (pinfunction "OUT_2") (pintype "power_in"))
      (node (ref "VD6") (pin "2") (pinfunction "A_2") (pintype "passive"))
    )
    (net (code "48") (name "Net-(VD10-A)") (class "Default")
      (node (ref "R23") (pin "1") (pinfunction "1_1") (pintype "passive"))
      (node (ref "VD10") (pin "2") (pinfunction "A_2") (pintype "passive"))
    )
    (net (code "49") (name "Net-(VD13-C)") (class "Default")
      (node (ref "C15") (pin "1") (pinfunction "1_1") (pintype "passive"))
      (node (ref "R10") (pin "2") (pinfunction "2_2") (pintype "passive"))
      (node (ref "VD13") (pin "1") (pinfunction "C_1") (pintype "passive"))
    )
    (net (code "50") (name "Net-(VD14-A)") (class "Default")
      (node (ref "R24") (pin "1") (pinfunction "1_1") (pintype "passive"))
      (node (ref "VD14") (pin "2") (pinfunction "A_2") (pintype "passive"))
    )
    (net (code "51") (name "Net-(VD16-C)") (class "Default")
      (node (ref "R24") (pin "2") (pinfunction "2_2") (pintype "passive"))
      (node (ref "R25") (pin "1") (pinfunction "1_1") (pintype "passive"))
      (node (ref "VD16") (pin "1") (pinfunction "C_1") (pintype "passive"))
      (node (ref "VD17") (pin "1") (pinfunction "C_1") (pintype "passive"))
    )
    (net (code "52") (name "unconnected-(K1-Pad4)") (class "Default")
      (node (ref "K1") (pin "4") (pinfunction "4_4") (pintype "passive"))
    )
    (net (code "53") (name "unconnected-(T1-Pad7)") (class "Default")
      (node (ref "T1") (pin "7") (pinfunction "7_7") (pintype "passive"))
    )
    (net (code "54") (name "unconnected-(T1-Pad9)") (class "Default")
      (node (ref "T1") (pin "9") (pinfunction "9_9") (pintype "passive"))
    )
  )
)
